# WifiLamp_Hardware_V2_0.net
KiCad netlist of a schematic drawn in EAGLE
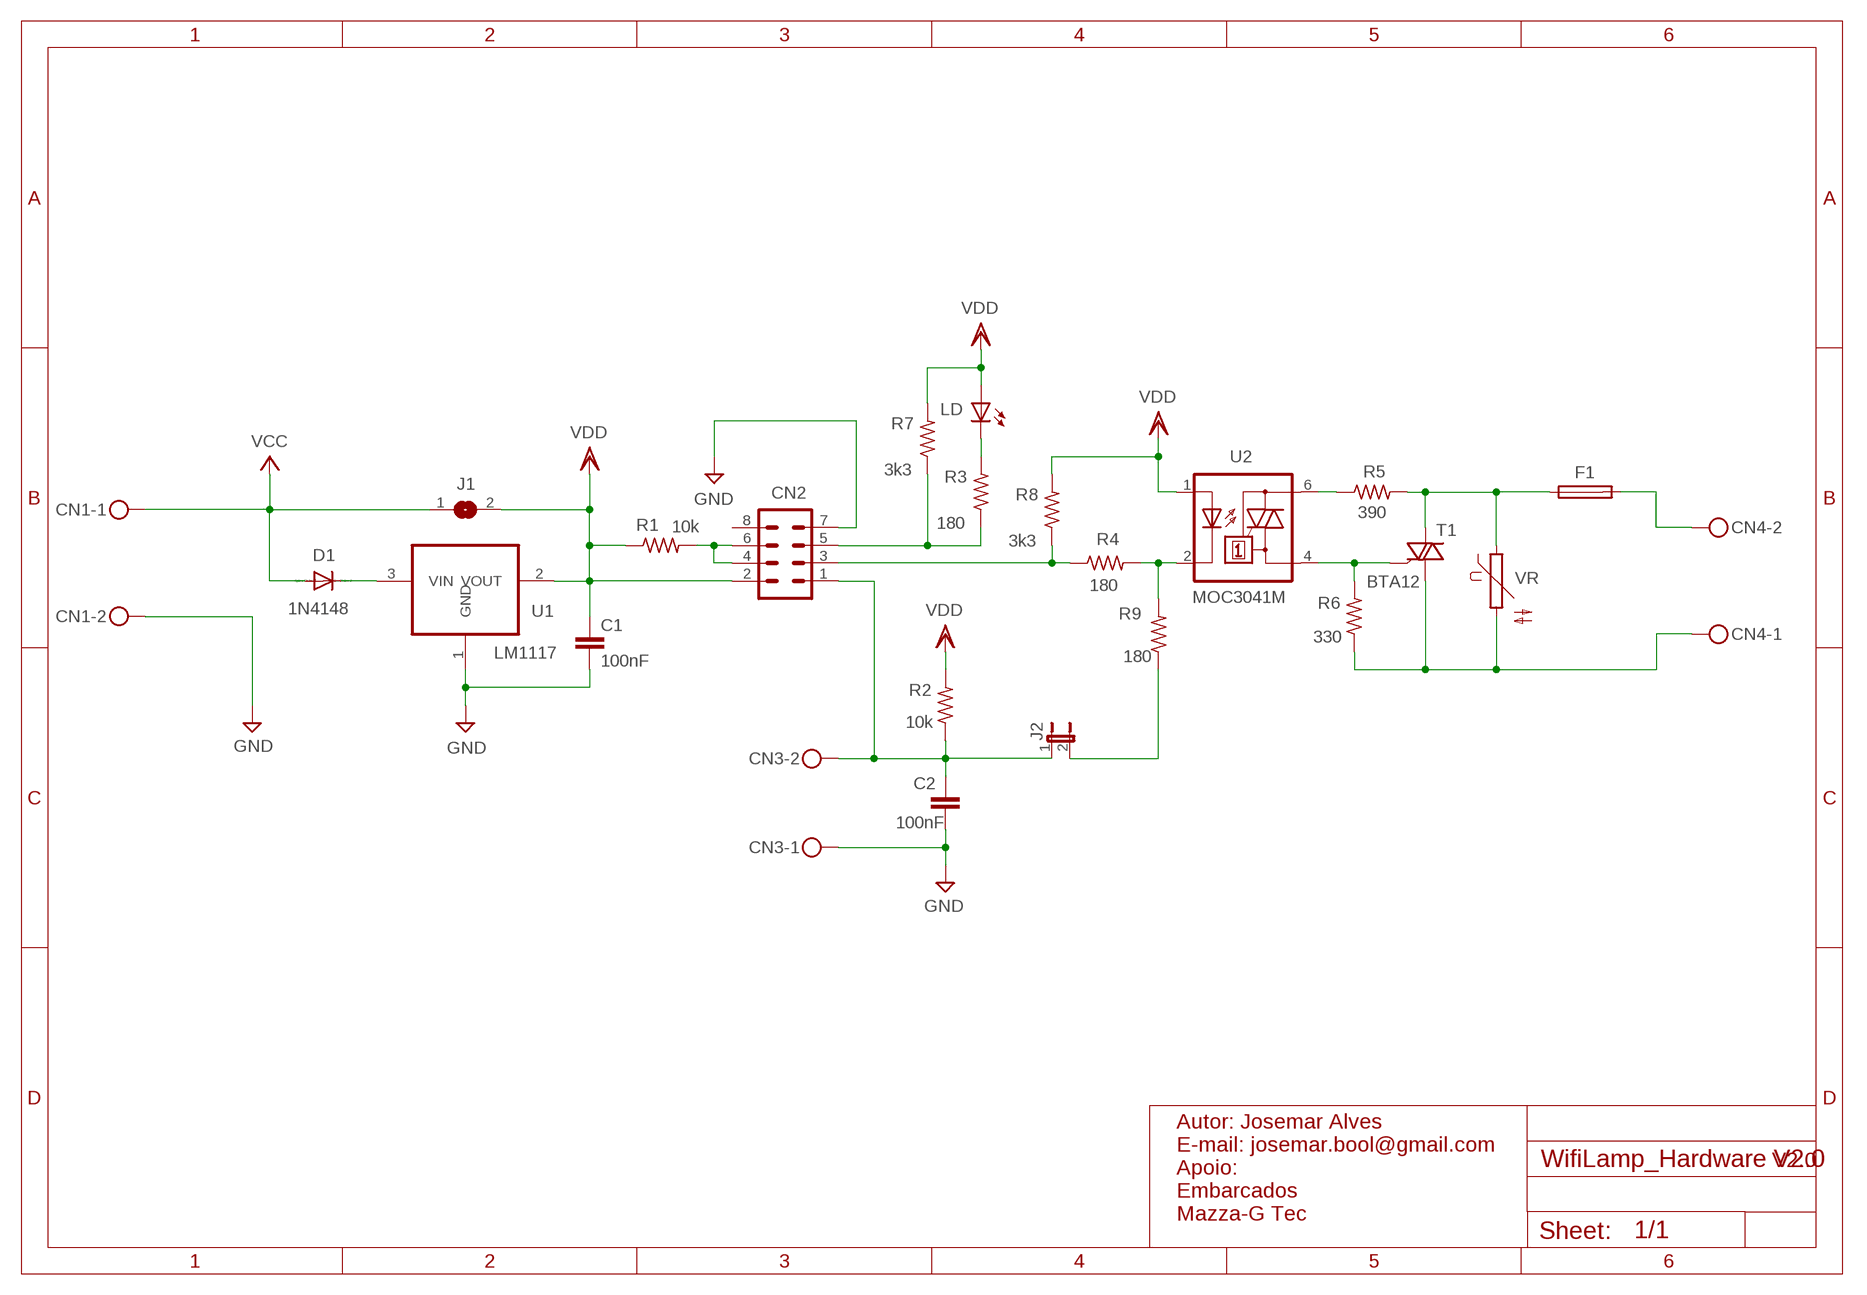
[diagram p0: schematic, sheet 1]

(export (version "E")
  (design (tool "Eeschema 10.0.6"))
  (components
    (comp (ref "C1")
      (value "100nF")
      (footprint "eagle-import:C0805K")
      (libsource (lib "eagle-import") (part "C-EUC0805K"))
    )
    (comp (ref "C2")
      (value "100nF")
      (footprint "eagle-import:C0805K")
      (libsource (lib "eagle-import") (part "C-EUC0805K"))
    )
    (comp (ref "CN1")
      (value "MKDSN1,5/2-5,08")
      (footprint "eagle-import:MKDSN1,5_2-5,08")
      (libsource (lib "eagle-import") (part "MKDSN1,5/2-5,08"))
    )
    (comp (ref "CN2")
      (value "MA04-2")
      (footprint "eagle-import:MA04-2")
      (libsource (lib "eagle-import") (part "MA04-2"))
    )
    (comp (ref "CN3")
      (value "MKDSN1,5/2-5,08")
      (footprint "eagle-import:MKDSN1,5_2-5,08")
      (libsource (lib "eagle-import") (part "MKDSN1,5/2-5,08"))
    )
    (comp (ref "CN4")
      (value "MKDSN1,5/2-5,08")
      (footprint "eagle-import:MKDSN1,5_2-5,08")
      (libsource (lib "eagle-import") (part "MKDSN1,5/2-5,08"))
    )
    (comp (ref "D1")
      (value "1N4148")
      (footprint "eagle-import:D-7.5")
      (libsource (lib "eagle-import") (part "DIODE-D-7.5"))
    )
    (comp (ref "F1")
      (value "FUSETR5")
      (footprint "eagle-import:TR5")
      (libsource (lib "eagle-import") (part "FUSETR5"))
    )
    (comp (ref "J1") (value "SJ") (footprint "eagle-import:SJ") (libsource (lib "eagle-import") (part "SJ")))
    (comp (ref "J2")
      (value "JP1E")
      (footprint "eagle-import:JP1")
      (libsource (lib "eagle-import") (part "JP1E"))
    )
    (comp (ref "LD")
      (value "LED3MM")
      (footprint "eagle-import:LED3MM")
      (libsource (lib "eagle-import") (part "LED3MM"))
    )
    (comp (ref "R1")
      (value "10k")
      (footprint "eagle-import:0309V")
      (libsource (lib "eagle-import") (part "R-US_0309/V"))
    )
    (comp (ref "R2")
      (value "10k")
      (footprint "eagle-import:0309V")
      (libsource (lib "eagle-import") (part "R-US_0309/V"))
    )
    (comp (ref "R3")
      (value "180")
      (footprint "eagle-import:0309V")
      (libsource (lib "eagle-import") (part "R-US_0309/V"))
    )
    (comp (ref "R4")
      (value "180")
      (footprint "eagle-import:0309V")
      (libsource (lib "eagle-import") (part "R-US_0309/V"))
    )
    (comp (ref "R5")
      (value "390")
      (footprint "eagle-import:0309V")
      (libsource (lib "eagle-import") (part "R-US_0309/V"))
    )
    (comp (ref "R6")
      (value "330")
      (footprint "eagle-import:0309V")
      (libsource (lib "eagle-import") (part "R-US_0309/V"))
    )
    (comp (ref "R7")
      (value "3k3")
      (footprint "eagle-import:0309V")
      (libsource (lib "eagle-import") (part "R-US_0309/V"))
    )
    (comp (ref "R8")
      (value "3k3")
      (footprint "eagle-import:0309V")
      (libsource (lib "eagle-import") (part "R-US_0309/V"))
    )
    (comp (ref "R9")
      (value "180")
      (footprint "eagle-import:0309V")
      (libsource (lib "eagle-import") (part "R-US_0309/V"))
    )
    (comp (ref "T1")
      (value "BTA12")
      (footprint "eagle-import:TO220BV")
      (libsource (lib "eagle-import") (part "BT138-V"))
    )
    (comp (ref "U1")
      (value "LM1117")
      (footprint "eagle-import:SOT223")
      (fields (field (name "MPN") "REG1117"))
      (libsource (lib "eagle-import") (part "REG1117"))
    )
    (comp (ref "U2")
      (value "MOC3041M")
      (footprint "eagle-import:DIL06")
      (fields (field (name "MF") "FAIRCHILD SEMICONDUCTOR"))
      (libsource (lib "eagle-import") (part "MOC3041M"))
    )
    (comp (ref "VR")
      (value "S07K230")
      (footprint "eagle-import:S07K230")
      (libsource (lib "eagle-import") (part "S07K230"))
    )
  )
  (nets
    (net (code "1") (name "GND") (class "Default")
      (node (ref "C1") (pin "2") (pinfunction "2_2") (pintype "passive"))
      (node (ref "C2") (pin "2") (pinfunction "2_2") (pintype "passive"))
      (node (ref "CN1") (pin "2") (pinfunction "KL_2") (pintype "passive"))
      (node (ref "CN2") (pin "7") (pinfunction "7_7") (pintype "passive"))
      (node (ref "CN3") (pin "1") (pinfunction "KL_1") (pintype "passive"))
      (node (ref "U1") (pin "1") (pinfunction "GND_1") (pintype "power_in"))
    )
    (net (code "2") (name "Net-(CN2-Pad3)") (class "Default")
      (node (ref "CN2") (pin "3") (pinfunction "3_3") (pintype "passive"))
      (node (ref "R4") (pin "1") (pinfunction "1_1") (pintype "passive"))
      (node (ref "R8") (pin "1") (pinfunction "1_1") (pintype "passive"))
    )
    (net (code "3") (name "Net-(CN2-Pad4)") (class "Default")
      (node (ref "CN2") (pin "4") (pinfunction "4_4") (pintype "passive"))
      (node (ref "CN2") (pin "6") (pinfunction "6_6") (pintype "passive"))
      (node (ref "R1") (pin "2") (pinfunction "2_2") (pintype "passive"))
    )
    (net (code "4") (name "Net-(CN2-Pad5)") (class "Default")
      (node (ref "CN2") (pin "5") (pinfunction "5_5") (pintype "passive"))
      (node (ref "R3") (pin "1") (pinfunction "1_1") (pintype "passive"))
      (node (ref "R7") (pin "1") (pinfunction "1_1") (pintype "passive"))
    )
    (net (code "5") (name "Net-(CN3B-KL)") (class "Default")
      (node (ref "C2") (pin "1") (pinfunction "1_1") (pintype "passive"))
      (node (ref "CN2") (pin "1") (pinfunction "1_1") (pintype "passive"))
      (node (ref "CN3") (pin "2") (pinfunction "KL_2") (pintype "passive"))
      (node (ref "J2") (pin "1") (pinfunction "1_1") (pintype "passive"))
      (node (ref "R2") (pin "1") (pinfunction "1_1") (pintype "passive"))
    )
    (net (code "6") (name "Net-(CN4A-KL)") (class "Default")
      (node (ref "CN4") (pin "1") (pinfunction "KL_1") (pintype "passive"))
      (node (ref "R6") (pin "1") (pinfunction "1_1") (pintype "passive"))
      (node (ref "T1") (pin "T1") (pinfunction "A1_T1") (pintype "passive"))
      (node (ref "VR") (pin "2") (pinfunction "2_2") (pintype "passive"))
    )
    (net (code "7") (name "Net-(CN4B-KL)") (class "Default")
      (node (ref "CN4") (pin "2") (pinfunction "KL_2") (pintype "passive"))
      (node (ref "F1") (pin "2") (pinfunction "2_2") (pintype "passive"))
    )
    (net (code "8") (name "Net-(J2-Pad2)") (class "Default")
      (node (ref "J2") (pin "2") (pinfunction "2_2") (pintype "passive"))
      (node (ref "R9") (pin "1") (pinfunction "1_1") (pintype "passive"))
    )
    (net (code "9") (name "Net-(LD-C)") (class "Default")
      (node (ref "LD") (pin "K") (pinfunction "C_K") (pintype "passive"))
      (node (ref "R3") (pin "2") (pinfunction "2_2") (pintype "passive"))
    )
    (net (code "10") (name "Net-(T1-A2)") (class "Default")
      (node (ref "F1") (pin "1") (pinfunction "1_1") (pintype "passive"))
      (node (ref "R5") (pin "2") (pinfunction "2_2") (pintype "passive"))
      (node (ref "T1") (pin "T2") (pinfunction "A2_T2") (pintype "passive"))
      (node (ref "VR") (pin "1") (pinfunction "1_1") (pintype "passive"))
    )
    (net (code "11") (name "Net-(U1-VIN)") (class "Default")
      (node (ref "D1") (pin "C") (pinfunction "C_C") (pintype "passive"))
      (node (ref "U1") (pin "3") (pinfunction "VIN_3") (pintype "input"))
    )
    (net (code "12") (name "Net-(U2-A1)") (class "Default")
      (node (ref "R6") (pin "2") (pinfunction "2_2") (pintype "passive"))
      (node (ref "T1") (pin "G") (pinfunction "G_G") (pintype "passive"))
      (node (ref "U2") (pin "4") (pinfunction "A1_4") (pintype "passive"))
    )
    (net (code "13") (name "Net-(U2-A2)") (class "Default")
      (node (ref "R5") (pin "1") (pinfunction "1_1") (pintype "passive"))
      (node (ref "U2") (pin "6") (pinfunction "A2_6") (pintype "passive"))
    )
    (net (code "14") (name "Net-(U2-C)") (class "Default")
      (node (ref "R4") (pin "2") (pinfunction "2_2") (pintype "passive"))
      (node (ref "R9") (pin "2") (pinfunction "2_2") (pintype "passive"))
      (node (ref "U2") (pin "2") (pinfunction "C_2") (pintype "passive"))
    )
    (net (code "15") (name "VCC") (class "Default")
      (node (ref "CN1") (pin "1") (pinfunction "KL_1") (pintype "passive"))
      (node (ref "D1") (pin "A") (pinfunction "A_A") (pintype "passive"))
      (node (ref "J1") (pin "1") (pinfunction "1_1") (pintype "passive"))
    )
    (net (code "16") (name "VDD") (class "Default")
      (node (ref "C1") (pin "1") (pinfunction "1_1") (pintype "passive"))
      (node (ref "CN2") (pin "2") (pinfunction "2_2") (pintype "passive"))
      (node (ref "J1") (pin "2") (pinfunction "2_2") (pintype "passive"))
      (node (ref "LD") (pin "A") (pinfunction "A_A") (pintype "passive"))
      (node (ref "R1") (pin "1") (pinfunction "1_1") (pintype "passive"))
      (node (ref "R2") (pin "2") (pinfunction "2_2") (pintype "passive"))
      (node (ref "R7") (pin "2") (pinfunction "2_2") (pintype "passive"))
      (node (ref "R8") (pin "2") (pinfunction "2_2") (pintype "passive"))
      (node (ref "U1") (pin "2") (pinfunction "VOUT_2") (pintype "output"))
      (node (ref "U2") (pin "1") (pinfunction "A_1") (pintype "passive"))
    )
    (net (code "17") (name "unconnected-(CN2-Pad8)") (class "Default")
      (node (ref "CN2") (pin "8") (pinfunction "8_8") (pintype "passive"))
    )
  )
)
